# esp32_power_supply.net
KiCad netlist of a schematic drawn in EAGLE
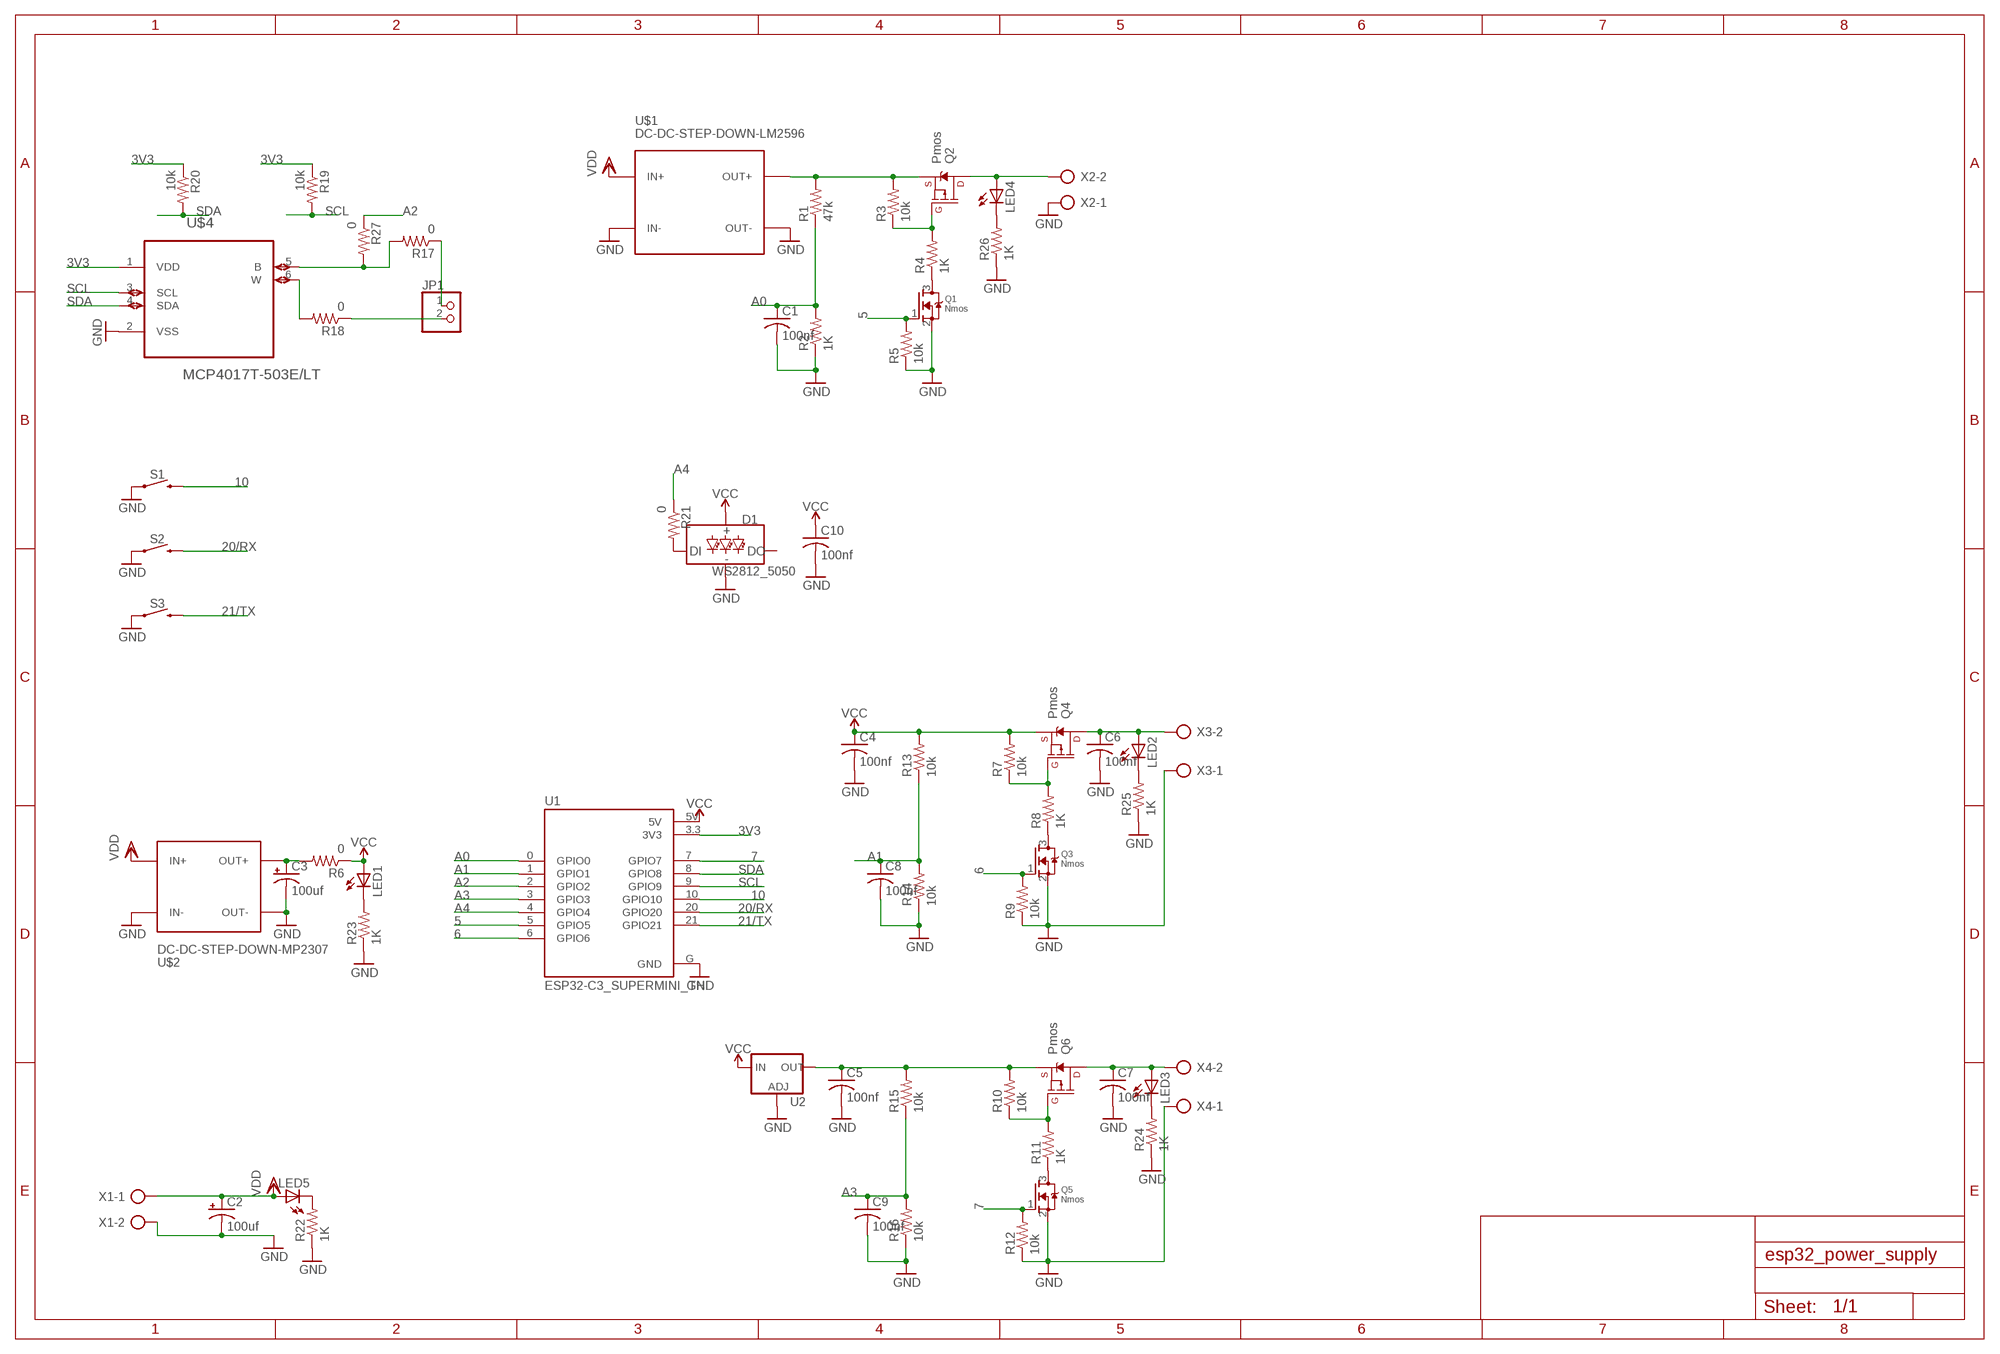
[diagram p0: schematic, sheet 1]

(export (version "E")
  (design (tool "Eeschema 10.0.6"))
  (components
    (comp (ref "C1")
      (value "100nf")
      (footprint "eagle-import:C1206K")
      (libsource (lib "eagle-import") (part "C-USC1206K"))
    )
    (comp (ref "C2")
      (value "100uf")
      (footprint "eagle-import:E3,5-10")
      (libsource (lib "eagle-import") (part "CPOL-USE3.5-10"))
    )
    (comp (ref "C3")
      (value "100uf")
      (footprint "eagle-import:E3,5-10")
      (libsource (lib "eagle-import") (part "CPOL-USE3.5-10"))
    )
    (comp (ref "C4")
      (value "100nf")
      (footprint "eagle-import:C1206K")
      (libsource (lib "eagle-import") (part "C-USC1206K"))
    )
    (comp (ref "C5")
      (value "100nf")
      (footprint "eagle-import:C1206K")
      (libsource (lib "eagle-import") (part "C-USC1206K"))
    )
    (comp (ref "C6")
      (value "100nf")
      (footprint "eagle-import:C1206K")
      (libsource (lib "eagle-import") (part "C-USC1206K"))
    )
    (comp (ref "C7")
      (value "100nf")
      (footprint "eagle-import:C1206K")
      (libsource (lib "eagle-import") (part "C-USC1206K"))
    )
    (comp (ref "C8")
      (value "100nf")
      (footprint "eagle-import:C1206K")
      (libsource (lib "eagle-import") (part "C-USC1206K"))
    )
    (comp (ref "C9")
      (value "100nf")
      (footprint "eagle-import:C1206K")
      (libsource (lib "eagle-import") (part "C-USC1206K"))
    )
    (comp (ref "C10")
      (value "100nf")
      (footprint "eagle-import:C1206K")
      (libsource (lib "eagle-import") (part "C-USC1206K"))
    )
    (comp (ref "D1")
      (value "WS2812_5050")
      (footprint "eagle-import:WS2812-5X5-4PIN")
      (libsource (lib "eagle-import") (part "WS2812_5050"))
    )
    (comp (ref "JP1")
      (value "PINHD-1X2")
      (footprint "eagle-import:1X02")
      (libsource (lib "eagle-import") (part "PINHD-1X2"))
    )
    (comp (ref "LED1")
      (value "LEDSMT1206")
      (footprint "eagle-import:1206")
      (libsource (lib "eagle-import") (part "LEDSMT1206"))
    )
    (comp (ref "LED2")
      (value "LEDSMT1206")
      (footprint "eagle-import:1206")
      (libsource (lib "eagle-import") (part "LEDSMT1206"))
    )
    (comp (ref "LED3")
      (value "LEDSMT1206")
      (footprint "eagle-import:1206")
      (libsource (lib "eagle-import") (part "LEDSMT1206"))
    )
    (comp (ref "LED4")
      (value "LEDSMT1206")
      (footprint "eagle-import:1206")
      (libsource (lib "eagle-import") (part "LEDSMT1206"))
    )
    (comp (ref "LED5")
      (value "LEDSMT1206")
      (footprint "eagle-import:1206")
      (libsource (lib "eagle-import") (part "LEDSMT1206"))
    )
    (comp (ref "Q1")
      (value "Nmos")
      (footprint "eagle-import:SOT23")
      (libsource (lib "eagle-import") (part "MOSFET-NREFLOW"))
    )
    (comp (ref "Q2")
      (value "Pmos")
      (footprint "eagle-import:SOT23-3")
      (libsource (lib "eagle-import") (part "MOSFET_PCH-SI2309DS"))
    )
    (comp (ref "Q3")
      (value "Nmos")
      (footprint "eagle-import:SOT23")
      (libsource (lib "eagle-import") (part "MOSFET-NREFLOW"))
    )
    (comp (ref "Q4")
      (value "Pmos")
      (footprint "eagle-import:SOT23-3")
      (libsource (lib "eagle-import") (part "MOSFET_PCH-SI2309DS"))
    )
    (comp (ref "Q5")
      (value "Nmos")
      (footprint "eagle-import:SOT23")
      (libsource (lib "eagle-import") (part "MOSFET-NREFLOW"))
    )
    (comp (ref "Q6")
      (value "Pmos")
      (footprint "eagle-import:SOT23-3")
      (libsource (lib "eagle-import") (part "MOSFET_PCH-SI2309DS"))
    )
    (comp (ref "R1")
      (value "47k")
      (footprint "eagle-import:M1206")
      (libsource (lib "eagle-import") (part "R-US_M1206"))
    )
    (comp (ref "R2")
      (value "1K")
      (footprint "eagle-import:M1206")
      (libsource (lib "eagle-import") (part "R-US_M1206"))
    )
    (comp (ref "R3")
      (value "10k")
      (footprint "eagle-import:M1206")
      (libsource (lib "eagle-import") (part "R-US_M1206"))
    )
    (comp (ref "R4")
      (value "1K")
      (footprint "eagle-import:M1206")
      (libsource (lib "eagle-import") (part "R-US_M1206"))
    )
    (comp (ref "R5")
      (value "10k")
      (footprint "eagle-import:M1206")
      (libsource (lib "eagle-import") (part "R-US_M1206"))
    )
    (comp (ref "R6")
      (value "0")
      (footprint "eagle-import:M1206")
      (libsource (lib "eagle-import") (part "R-US_M1206"))
    )
    (comp (ref "R7")
      (value "10k")
      (footprint "eagle-import:M1206")
      (libsource (lib "eagle-import") (part "R-US_M1206"))
    )
    (comp (ref "R8")
      (value "1K")
      (footprint "eagle-import:M1206")
      (libsource (lib "eagle-import") (part "R-US_M1206"))
    )
    (comp (ref "R9")
      (value "10k")
      (footprint "eagle-import:M1206")
      (libsource (lib "eagle-import") (part "R-US_M1206"))
    )
    (comp (ref "R10")
      (value "10k")
      (footprint "eagle-import:M1206")
      (libsource (lib "eagle-import") (part "R-US_M1206"))
    )
    (comp (ref "R11")
      (value "1K")
      (footprint "eagle-import:M1206")
      (libsource (lib "eagle-import") (part "R-US_M1206"))
    )
    (comp (ref "R12")
      (value "10k")
      (footprint "eagle-import:M1206")
      (libsource (lib "eagle-import") (part "R-US_M1206"))
    )
    (comp (ref "R13")
      (value "10k")
      (footprint "eagle-import:M1206")
      (libsource (lib "eagle-import") (part "R-US_M1206"))
    )
    (comp (ref "R14")
      (value "10k")
      (footprint "eagle-import:M1206")
      (libsource (lib "eagle-import") (part "R-US_M1206"))
    )
    (comp (ref "R15")
      (value "10k")
      (footprint "eagle-import:M1206")
      (libsource (lib "eagle-import") (part "R-US_M1206"))
    )
    (comp (ref "R16")
      (value "10k")
      (footprint "eagle-import:M1206")
      (libsource (lib "eagle-import") (part "R-US_M1206"))
    )
    (comp (ref "R17")
      (value "0")
      (footprint "eagle-import:M1206")
      (libsource (lib "eagle-import") (part "R-US_M1206"))
    )
    (comp (ref "R18")
      (value "0")
      (footprint "eagle-import:M1206")
      (libsource (lib "eagle-import") (part "R-US_M1206"))
    )
    (comp (ref "R19")
      (value "10k")
      (footprint "eagle-import:M1206")
      (libsource (lib "eagle-import") (part "R-US_M1206"))
    )
    (comp (ref "R20")
      (value "10k")
      (footprint "eagle-import:M1206")
      (libsource (lib "eagle-import") (part "R-US_M1206"))
    )
    (comp (ref "R21")
      (value "0")
      (footprint "eagle-import:M1206")
      (libsource (lib "eagle-import") (part "R-US_M1206"))
    )
    (comp (ref "R22")
      (value "1K")
      (footprint "eagle-import:M1206")
      (libsource (lib "eagle-import") (part "R-US_M1206"))
    )
    (comp (ref "R23")
      (value "1K")
      (footprint "eagle-import:M1206")
      (libsource (lib "eagle-import") (part "R-US_M1206"))
    )
    (comp (ref "R24")
      (value "1K")
      (footprint "eagle-import:M1206")
      (libsource (lib "eagle-import") (part "R-US_M1206"))
    )
    (comp (ref "R25")
      (value "1K")
      (footprint "eagle-import:M1206")
      (libsource (lib "eagle-import") (part "R-US_M1206"))
    )
    (comp (ref "R26")
      (value "1K")
      (footprint "eagle-import:M1206")
      (libsource (lib "eagle-import") (part "R-US_M1206"))
    )
    (comp (ref "R27")
      (value "0")
      (footprint "eagle-import:M1206")
      (libsource (lib "eagle-import") (part "R-US_M1206"))
    )
    (comp (ref "S1")
      (value "MOMENTARY-SWITCH-SPST-PTH-6.0MM")
      (footprint "eagle-import:TACTILE_SWITCH_PTH_6.0MM")
      (libsource (lib "eagle-import") (part "MOMENTARY-SWITCH-SPST-PTH-6.0MM"))
    )
    (comp (ref "S2")
      (value "MOMENTARY-SWITCH-SPST-PTH-6.0MM")
      (footprint "eagle-import:TACTILE_SWITCH_PTH_6.0MM")
      (libsource (lib "eagle-import") (part "MOMENTARY-SWITCH-SPST-PTH-6.0MM"))
    )
    (comp (ref "S3")
      (value "MOMENTARY-SWITCH-SPST-PTH-6.0MM")
      (footprint "eagle-import:TACTILE_SWITCH_PTH_6.0MM")
      (libsource (lib "eagle-import") (part "MOMENTARY-SWITCH-SPST-PTH-6.0MM"))
    )
    (comp (ref "U$1")
      (value "DC-DC-STEP-DOWN-LM2596")
      (footprint "eagle-import:DC-DC-STEP-DOWN-LM2596")
      (libsource (lib "eagle-import") (part "DC-DC-STEP-DOWN-LM2596"))
    )
    (comp (ref "U$2")
      (value "DC-DC-STEP-DOWN-MP2307")
      (footprint "eagle-import:DC-DC-STEP-DOWN-MP2307")
      (libsource (lib "eagle-import") (part "DC-DC-STEP-DOWN-MP2307"))
    )
    (comp (ref "U$4")
      (value "MCP4017T-503E/LT")
      (footprint "eagle-import:SOT65P210X110-6N")
      (fields (field (name "MF") "Microchip"))
      (libsource (lib "eagle-import") (part "MCP4017T-503E/LT"))
    )
    (comp (ref "U1")
      (value "ESP32-C3_SUPERMINI_TH")
      (footprint "eagle-import:MODULE_ESP32-C3_SUPERMINI_TH")
      (fields (field (name "MF") "Espressif Systems") (field (name "MP") "ESP32-C3 SuperMini_TH"))
      (libsource (lib "eagle-import") (part "ESP32-C3_SUPERMINI_TH"))
    )
    (comp (ref "U2")
      (value "V_REG_LM1117SOT223")
      (footprint "eagle-import:SOT223")
      (libsource (lib "eagle-import") (part "V_REG_LM1117SOT223"))
    )
    (comp (ref "X1")
      (value "AK500/2-H")
      (footprint "eagle-import:AK500_2-H")
      (libsource (lib "eagle-import") (part "AK500/2-H"))
    )
    (comp (ref "X2")
      (value "AK500/2-H")
      (footprint "eagle-import:AK500_2-H")
      (libsource (lib "eagle-import") (part "AK500/2-H"))
    )
    (comp (ref "X3")
      (value "AK500/2-H")
      (footprint "eagle-import:AK500_2-H")
      (libsource (lib "eagle-import") (part "AK500/2-H"))
    )
    (comp (ref "X4")
      (value "AK500/2-H")
      (footprint "eagle-import:AK500_2-H")
      (libsource (lib "eagle-import") (part "AK500/2-H"))
    )
  )
  (nets
    (net (code "1") (name "/3V3") (class "Default")
      (node (ref "R19") (pin "1") (pinfunction "1_1") (pintype "passive"))
      (node (ref "R20") (pin "1") (pinfunction "1_1") (pintype "passive"))
      (node (ref "U$4") (pin "1") (pinfunction "VDD_1") (pintype "power_in"))
      (node (ref "U1") (pin "3.3") (pinfunction "3V3_3.3") (pintype "power_in"))
    )
    (net (code "2") (name "/5") (class "Default")
      (node (ref "Q1") (pin "1") (pinfunction "G_1") (pintype "bidirectional"))
      (node (ref "R5") (pin "2") (pinfunction "2_2") (pintype "passive"))
      (node (ref "U1") (pin "5") (pinfunction "GPIO5_5") (pintype "bidirectional"))
    )
    (net (code "3") (name "/6") (class "Default")
      (node (ref "Q3") (pin "1") (pinfunction "G_1") (pintype "bidirectional"))
      (node (ref "R9") (pin "2") (pinfunction "2_2") (pintype "passive"))
      (node (ref "U1") (pin "6") (pinfunction "GPIO6_6") (pintype "bidirectional"))
    )
    (net (code "4") (name "/7") (class "Default")
      (node (ref "Q5") (pin "1") (pinfunction "G_1") (pintype "bidirectional"))
      (node (ref "R12") (pin "2") (pinfunction "2_2") (pintype "passive"))
      (node (ref "U1") (pin "7") (pinfunction "GPIO7_7") (pintype "bidirectional"))
    )
    (net (code "5") (name "/10") (class "Default")
      (node (ref "S1") (pin "3") (pinfunction "2_3") (pintype "passive"))
      (node (ref "U1") (pin "10") (pinfunction "GPIO10_10") (pintype "bidirectional"))
    )
    (net (code "6") (name "/20{slash}RX") (class "Default")
      (node (ref "S2") (pin "3") (pinfunction "2_3") (pintype "passive"))
      (node (ref "U1") (pin "20") (pinfunction "GPIO20_20") (pintype "bidirectional"))
    )
    (net (code "7") (name "/21{slash}TX") (class "Default")
      (node (ref "S3") (pin "3") (pinfunction "2_3") (pintype "passive"))
      (node (ref "U1") (pin "21") (pinfunction "GPIO21_21") (pintype "bidirectional"))
    )
    (net (code "8") (name "/A0") (class "Default")
      (node (ref "C1") (pin "1") (pinfunction "1_1") (pintype "passive"))
      (node (ref "R1") (pin "1") (pinfunction "1_1") (pintype "passive"))
      (node (ref "R2") (pin "2") (pinfunction "2_2") (pintype "passive"))
      (node (ref "U1") (pin "0") (pinfunction "GPIO0_0") (pintype "bidirectional"))
    )
    (net (code "9") (name "/A1") (class "Default")
      (node (ref "C8") (pin "1") (pinfunction "1_1") (pintype "passive"))
      (node (ref "R13") (pin "1") (pinfunction "1_1") (pintype "passive"))
      (node (ref "R14") (pin "2") (pinfunction "2_2") (pintype "passive"))
      (node (ref "U1") (pin "1") (pinfunction "GPIO1_1") (pintype "bidirectional"))
    )
    (net (code "10") (name "/A2") (class "Default")
      (node (ref "R27") (pin "1") (pinfunction "1_1") (pintype "passive"))
      (node (ref "U1") (pin "2") (pinfunction "GPIO2_2") (pintype "bidirectional"))
    )
    (net (code "11") (name "/A3") (class "Default")
      (node (ref "C9") (pin "1") (pinfunction "1_1") (pintype "passive"))
      (node (ref "R15") (pin "1") (pinfunction "1_1") (pintype "passive"))
      (node (ref "R16") (pin "2") (pinfunction "2_2") (pintype "passive"))
      (node (ref "U1") (pin "3") (pinfunction "GPIO3_3") (pintype "bidirectional"))
    )
    (net (code "12") (name "/A4") (class "Default")
      (node (ref "R21") (pin "1") (pinfunction "1_1") (pintype "passive"))
      (node (ref "U1") (pin "4") (pinfunction "GPIO4_4") (pintype "bidirectional"))
    )
    (net (code "13") (name "/SCL") (class "Default")
      (node (ref "R19") (pin "2") (pinfunction "2_2") (pintype "passive"))
      (node (ref "U$4") (pin "3") (pinfunction "SCL_3") (pintype "bidirectional"))
      (node (ref "U1") (pin "9") (pinfunction "GPIO9_9") (pintype "bidirectional"))
    )
    (net (code "14") (name "/SDA") (class "Default")
      (node (ref "R20") (pin "2") (pinfunction "2_2") (pintype "passive"))
      (node (ref "U$4") (pin "4") (pinfunction "SDA_4") (pintype "bidirectional"))
      (node (ref "U1") (pin "8") (pinfunction "GPIO8_8") (pintype "bidirectional"))
    )
    (net (code "15") (name "GND") (class "Default")
      (node (ref "C1") (pin "2") (pinfunction "2_2") (pintype "passive"))
      (node (ref "C10") (pin "2") (pinfunction "2_2") (pintype "passive"))
      (node (ref "C2") (pin "-") (pinfunction "-_-") (pintype "passive"))
      (node (ref "C3") (pin "-") (pinfunction "-_-") (pintype "passive"))
      (node (ref "C4") (pin "2") (pinfunction "2_2") (pintype "passive"))
      (node (ref "C5") (pin "2") (pinfunction "2_2") (pintype "passive"))
      (node (ref "C6") (pin "2") (pinfunction "2_2") (pintype "passive"))
      (node (ref "C7") (pin "2") (pinfunction "2_2") (pintype "passive"))
      (node (ref "C8") (pin "2") (pinfunction "2_2") (pintype "passive"))
      (node (ref "C9") (pin "2") (pinfunction "2_2") (pintype "passive"))
      (node (ref "D1") (pin "GND") (pinfunction "GND_GND") (pintype "bidirectional"))
      (node (ref "Q1") (pin "2") (pinfunction "S_2") (pintype "bidirectional"))
      (node (ref "Q3") (pin "2") (pinfunction "S_2") (pintype "bidirectional"))
      (node (ref "Q5") (pin "2") (pinfunction "S_2") (pintype "bidirectional"))
      (node (ref "R12") (pin "1") (pinfunction "1_1") (pintype "passive"))
      (node (ref "R14") (pin "1") (pinfunction "1_1") (pintype "passive"))
      (node (ref "R16") (pin "1") (pinfunction "1_1") (pintype "passive"))
      (node (ref "R2") (pin "1") (pinfunction "1_1") (pintype "passive"))
      (node (ref "R22") (pin "1") (pinfunction "1_1") (pintype "passive"))
      (node (ref "R23") (pin "1") (pinfunction "1_1") (pintype "passive"))
      (node (ref "R24") (pin "1") (pinfunction "1_1") (pintype "passive"))
      (node (ref "R25") (pin "1") (pinfunction "1_1") (pintype "passive"))
      (node (ref "R26") (pin "1") (pinfunction "1_1") (pintype "passive"))
      (node (ref "R5") (pin "1") (pinfunction "1_1") (pintype "passive"))
      (node (ref "R9") (pin "1") (pinfunction "1_1") (pintype "passive"))
      (node (ref "S1") (pin "1") (pinfunction "1_1") (pintype "passive"))
      (node (ref "S2") (pin "1") (pinfunction "1_1") (pintype "passive"))
      (node (ref "S3") (pin "1") (pinfunction "1_1") (pintype "passive"))
      (node (ref "U$1") (pin "IN-") (pinfunction "IN-_IN-") (pintype "bidirectional"))
      (node (ref "U$1") (pin "OUT-") (pinfunction "OUT-_OUT-") (pintype "bidirectional"))
      (node (ref "U$2") (pin "IN-") (pinfunction "IN-_IN-") (pintype "bidirectional"))
      (node (ref "U$2") (pin "OUT-") (pinfunction "OUT-_OUT-") (pintype "bidirectional"))
      (node (ref "U$4") (pin "2") (pinfunction "VSS_2") (pintype "power_in"))
      (node (ref "U1") (pin "G") (pinfunction "GND_G") (pintype "power_in"))
      (node (ref "U2") (pin "1") (pinfunction "ADJ_1") (pintype "input"))
      (node (ref "X1") (pin "2") (pinfunction "KL_2") (pintype "passive"))
      (node (ref "X2") (pin "1") (pinfunction "KL_1") (pintype "passive"))
      (node (ref "X3") (pin "1") (pinfunction "KL_1") (pintype "passive"))
      (node (ref "X4") (pin "1") (pinfunction "KL_1") (pintype "passive"))
    )
    (net (code "16") (name "Net-(C3-Pad+)") (class "Default")
      (node (ref "C3") (pin "+") (pinfunction "+_+") (pintype "passive"))
      (node (ref "R6") (pin "2") (pinfunction "2_2") (pintype "passive"))
      (node (ref "U$2") (pin "OUT+") (pinfunction "OUT+_OUT+") (pintype "bidirectional"))
    )
    (net (code "17") (name "Net-(D1-PadDI)") (class "Default")
      (node (ref "D1") (pin "DI") (pinfunction "DI_DI") (pintype "bidirectional"))
      (node (ref "R21") (pin "2") (pinfunction "2_2") (pintype "passive"))
    )
    (net (code "18") (name "Net-(JP1-Pad1)") (class "Default")
      (node (ref "JP1") (pin "1") (pinfunction "1_1") (pintype "passive"))
      (node (ref "R17") (pin "1") (pinfunction "1_1") (pintype "passive"))
    )
    (net (code "19") (name "Net-(JP1-Pad2)") (class "Default")
      (node (ref "JP1") (pin "2") (pinfunction "2_2") (pintype "passive"))
      (node (ref "R18") (pin "1") (pinfunction "1_1") (pintype "passive"))
    )
    (net (code "20") (name "Net-(LED1-PadC)") (class "Default")
      (node (ref "LED1") (pin "C") (pinfunction "C_C") (pintype "passive"))
      (node (ref "R23") (pin "2") (pinfunction "2_2") (pintype "passive"))
    )
    (net (code "21") (name "Net-(LED2-PadC)") (class "Default")
      (node (ref "LED2") (pin "C") (pinfunction "C_C") (pintype "passive"))
      (node (ref "R25") (pin "2") (pinfunction "2_2") (pintype "passive"))
    )
    (net (code "22") (name "Net-(LED3-PadC)") (class "Default")
      (node (ref "LED3") (pin "C") (pinfunction "C_C") (pintype "passive"))
      (node (ref "R24") (pin "2") (pinfunction "2_2") (pintype "passive"))
    )
    (net (code "23") (name "Net-(LED4-PadC)") (class "Default")
      (node (ref "LED4") (pin "C") (pinfunction "C_C") (pintype "passive"))
      (node (ref "R26") (pin "2") (pinfunction "2_2") (pintype "passive"))
    )
    (net (code "24") (name "Net-(LED5-PadC)") (class "Default")
      (node (ref "LED5") (pin "C") (pinfunction "C_C") (pintype "passive"))
      (node (ref "R22") (pin "2") (pinfunction "2_2") (pintype "passive"))
    )
    (net (code "25") (name "Net-(Q1-D)") (class "Default")
      (node (ref "Q1") (pin "3") (pinfunction "D_3") (pintype "bidirectional"))
      (node (ref "R4") (pin "1") (pinfunction "1_1") (pintype "passive"))
    )
    (net (code "26") (name "Net-(Q2-D)") (class "Default")
      (node (ref "LED4") (pin "A") (pinfunction "A_A") (pintype "passive"))
      (node (ref "Q2") (pin "3") (pinfunction "D_3") (pintype "bidirectional"))
      (node (ref "X2") (pin "2") (pinfunction "KL_2") (pintype "passive"))
    )
    (net (code "27") (name "Net-(Q2-G)") (class "Default")
      (node (ref "Q2") (pin "1") (pinfunction "G_1") (pintype "bidirectional"))
      (node (ref "R3") (pin "1") (pinfunction "1_1") (pintype "passive"))
      (node (ref "R4") (pin "2") (pinfunction "2_2") (pintype "passive"))
    )
    (net (code "28") (name "Net-(Q2-S)") (class "Default")
      (node (ref "Q2") (pin "2") (pinfunction "S_2") (pintype "bidirectional"))
      (node (ref "R1") (pin "2") (pinfunction "2_2") (pintype "passive"))
      (node (ref "R3") (pin "2") (pinfunction "2_2") (pintype "passive"))
      (node (ref "U$1") (pin "OUT+") (pinfunction "OUT+_OUT+") (pintype "bidirectional"))
    )
    (net (code "29") (name "Net-(Q3-D)") (class "Default")
      (node (ref "Q3") (pin "3") (pinfunction "D_3") (pintype "bidirectional"))
      (node (ref "R8") (pin "1") (pinfunction "1_1") (pintype "passive"))
    )
    (net (code "30") (name "Net-(Q4-D)") (class "Default")
      (node (ref "C6") (pin "1") (pinfunction "1_1") (pintype "passive"))
      (node (ref "LED2") (pin "A") (pinfunction "A_A") (pintype "passive"))
      (node (ref "Q4") (pin "3") (pinfunction "D_3") (pintype "bidirectional"))
      (node (ref "X3") (pin "2") (pinfunction "KL_2") (pintype "passive"))
    )
    (net (code "31") (name "Net-(Q4-G)") (class "Default")
      (node (ref "Q4") (pin "1") (pinfunction "G_1") (pintype "bidirectional"))
      (node (ref "R7") (pin "1") (pinfunction "1_1") (pintype "passive"))
      (node (ref "R8") (pin "2") (pinfunction "2_2") (pintype "passive"))
    )
    (net (code "32") (name "Net-(Q5-D)") (class "Default")
      (node (ref "Q5") (pin "3") (pinfunction "D_3") (pintype "bidirectional"))
      (node (ref "R11") (pin "1") (pinfunction "1_1") (pintype "passive"))
    )
    (net (code "33") (name "Net-(Q6-D)") (class "Default")
      (node (ref "C7") (pin "1") (pinfunction "1_1") (pintype "passive"))
      (node (ref "LED3") (pin "A") (pinfunction "A_A") (pintype "passive"))
      (node (ref "Q6") (pin "3") (pinfunction "D_3") (pintype "bidirectional"))
      (node (ref "X4") (pin "2") (pinfunction "KL_2") (pintype "passive"))
    )
    (net (code "34") (name "Net-(Q6-G)") (class "Default")
      (node (ref "Q6") (pin "1") (pinfunction "G_1") (pintype "bidirectional"))
      (node (ref "R10") (pin "1") (pinfunction "1_1") (pintype "passive"))
      (node (ref "R11") (pin "2") (pinfunction "2_2") (pintype "passive"))
    )
    (net (code "35") (name "Net-(Q6-S)") (class "Default")
      (node (ref "C5") (pin "1") (pinfunction "1_1") (pintype "passive"))
      (node (ref "Q6") (pin "2") (pinfunction "S_2") (pintype "bidirectional"))
      (node (ref "R10") (pin "2") (pinfunction "2_2") (pintype "passive"))
      (node (ref "R15") (pin "2") (pinfunction "2_2") (pintype "passive"))
      (node (ref "U2") (pin "2") (pinfunction "OUT_2") (pintype "output"))
      (node (ref "U2") (pin "4") (pinfunction "OUT_4") (pintype "output"))
    )
    (net (code "36") (name "Net-(U$4-B)") (class "Default")
      (node (ref "R17") (pin "2") (pinfunction "2_2") (pintype "passive"))
      (node (ref "R27") (pin "2") (pinfunction "2_2") (pintype "passive"))
      (node (ref "U$4") (pin "5") (pinfunction "B_5") (pintype "bidirectional"))
    )
    (net (code "37") (name "Net-(U$4-W)") (class "Default")
      (node (ref "R18") (pin "2") (pinfunction "2_2") (pintype "passive"))
      (node (ref "U$4") (pin "6") (pinfunction "W_6") (pintype "bidirectional"))
    )
    (net (code "38") (name "VCC") (class "Default")
      (node (ref "C10") (pin "1") (pinfunction "1_1") (pintype "passive"))
      (node (ref "C4") (pin "1") (pinfunction "1_1") (pintype "passive"))
      (node (ref "D1") (pin "VCC") (pinfunction "VCC_VCC") (pintype "bidirectional"))
      (node (ref "LED1") (pin "A") (pinfunction "A_A") (pintype "passive"))
      (node (ref "Q4") (pin "2") (pinfunction "S_2") (pintype "bidirectional"))
      (node (ref "R13") (pin "2") (pinfunction "2_2") (pintype "passive"))
      (node (ref "R6") (pin "1") (pinfunction "1_1") (pintype "passive"))
      (node (ref "R7") (pin "2") (pinfunction "2_2") (pintype "passive"))
      (node (ref "U1") (pin "5V") (pinfunction "5V_5V") (pintype "power_in"))
      (node (ref "U2") (pin "3") (pinfunction "IN_3") (pintype "input"))
    )
    (net (code "39") (name "VDD") (class "Default")
      (node (ref "C2") (pin "+") (pinfunction "+_+") (pintype "passive"))
      (node (ref "LED5") (pin "A") (pinfunction "A_A") (pintype "passive"))
      (node (ref "U$1") (pin "IN+") (pinfunction "IN+_IN+") (pintype "bidirectional"))
      (node (ref "U$2") (pin "IN+") (pinfunction "IN+_IN+") (pintype "bidirectional"))
      (node (ref "X1") (pin "1") (pinfunction "KL_1") (pintype "passive"))
    )
    (net (code "40") (name "unconnected-(D1-PadDO)") (class "Default")
      (node (ref "D1") (pin "DO") (pinfunction "DO_DO") (pintype "bidirectional"))
    )
  )
)
